# v6_io_27_28_32_33.net
KiCad netlist of a schematic drawn in Altium Designer
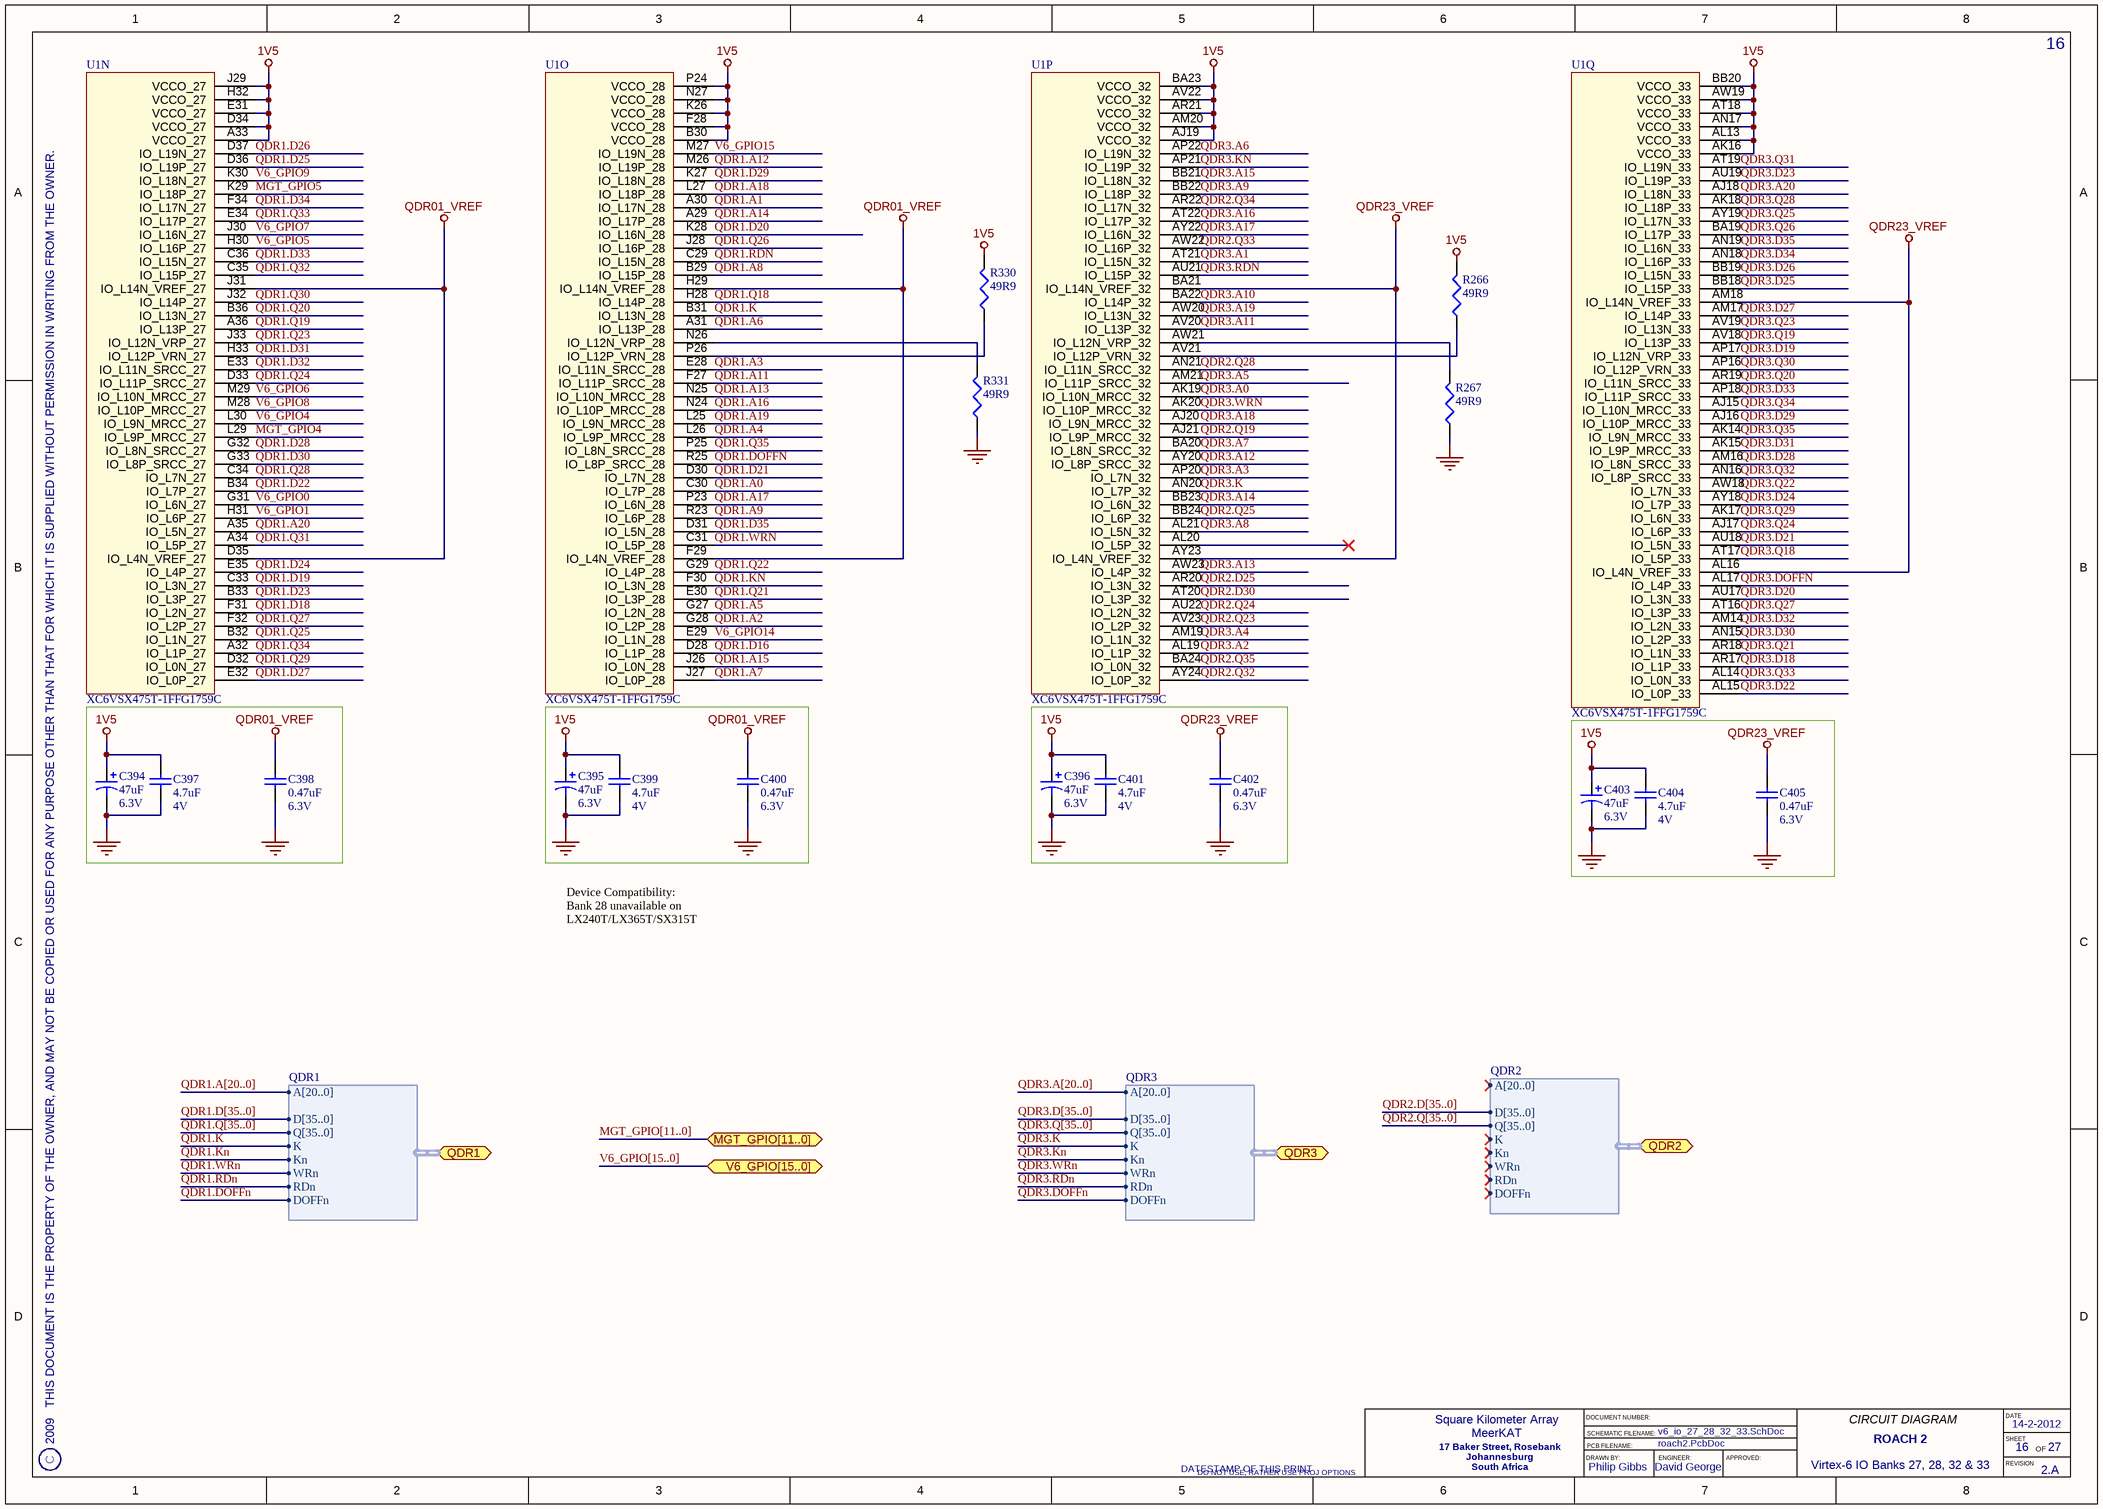
[diagram p0: v6_io_27_28_32_33.SchDoc]

(export (version "E")
  (design (tool "Eeschema 10.0.6"))
  (components
    (comp (ref "C394")
      (value "47uF")
      (footprint "CAPMP3528X120L")
      (description "47uF, Conductive Polymer Chip Capacitor")
      (fields
        (field (name "RATING") "6.3V")
        (field (name "MANUFACTURER") "KEMET")
        (field (name "PARTNUM") "T520T476M006ATE070")
      )
      (libsource (lib "altium_db") (part "CapPol"))
    )
    (comp (ref "C395")
      (value "47uF")
      (footprint "CAPMP3528X120L")
      (description "47uF, Conductive Polymer Chip Capacitor")
      (fields
        (field (name "RATING") "6.3V")
        (field (name "MANUFACTURER") "KEMET")
        (field (name "PARTNUM") "T520T476M006ATE070")
      )
      (libsource (lib "altium_db") (part "CapPol"))
    )
    (comp (ref "C396")
      (value "47uF")
      (footprint "CAPMP3528X120L")
      (description "47uF, Conductive Polymer Chip Capacitor")
      (fields
        (field (name "RATING") "6.3V")
        (field (name "MANUFACTURER") "KEMET")
        (field (name "PARTNUM") "T520T476M006ATE070")
      )
      (libsource (lib "altium_db") (part "CapPol"))
    )
    (comp (ref "C397")
      (value "4.7uF")
      (footprint "CAPC1005X60L")
      (description "4.7uF, Ceramic Capacitor")
      (fields
        (field (name "RATING") "4V")
        (field (name "MANUFACTURER") "MURATA")
        (field (name "PARTNUM") "AMK105BJ475MV-F")
      )
      (libsource (lib "altium_db") (part "CapStd"))
    )
    (comp (ref "C398")
      (value "0.47uF")
      (footprint "CAPC1005X55L")
      (description "0.47uF, Ceramic Capacitor")
      (fields
        (field (name "RATING") "6.3V")
        (field (name "MANUFACTURER") "MURATA")
        (field (name "PARTNUM") "GRM155R60J474KE19")
      )
      (libsource (lib "altium_db") (part "CapStd"))
    )
    (comp (ref "C399")
      (value "4.7uF")
      (footprint "CAPC1005X60L")
      (description "4.7uF, Ceramic Capacitor")
      (fields
        (field (name "RATING") "4V")
        (field (name "MANUFACTURER") "MURATA")
        (field (name "PARTNUM") "AMK105BJ475MV-F")
      )
      (libsource (lib "altium_db") (part "CapStd"))
    )
    (comp (ref "C400")
      (value "0.47uF")
      (footprint "CAPC1005X55L")
      (description "0.47uF, Ceramic Capacitor")
      (fields
        (field (name "RATING") "6.3V")
        (field (name "MANUFACTURER") "MURATA")
        (field (name "PARTNUM") "GRM155R60J474KE19")
      )
      (libsource (lib "altium_db") (part "CapStd"))
    )
    (comp (ref "C401")
      (value "4.7uF")
      (footprint "CAPC1005X60L")
      (description "4.7uF, Ceramic Capacitor")
      (fields
        (field (name "RATING") "4V")
        (field (name "MANUFACTURER") "MURATA")
        (field (name "PARTNUM") "AMK105BJ475MV-F")
      )
      (libsource (lib "altium_db") (part "CapStd"))
    )
    (comp (ref "C402")
      (value "0.47uF")
      (footprint "CAPC1005X55L")
      (description "0.47uF, Ceramic Capacitor")
      (fields
        (field (name "RATING") "6.3V")
        (field (name "MANUFACTURER") "MURATA")
        (field (name "PARTNUM") "GRM155R60J474KE19")
      )
      (libsource (lib "altium_db") (part "CapStd"))
    )
    (comp (ref "C403")
      (value "47uF")
      (footprint "CAPMP3528X120L")
      (description "47uF, Conductive Polymer Chip Capacitor")
      (fields
        (field (name "RATING") "6.3V")
        (field (name "MANUFACTURER") "KEMET")
        (field (name "PARTNUM") "T520T476M006ATE070")
      )
      (libsource (lib "altium_db") (part "CapPol"))
    )
    (comp (ref "C404")
      (value "4.7uF")
      (footprint "CAPC1005X60L")
      (description "4.7uF, Ceramic Capacitor")
      (fields
        (field (name "RATING") "4V")
        (field (name "MANUFACTURER") "MURATA")
        (field (name "PARTNUM") "AMK105BJ475MV-F")
      )
      (libsource (lib "altium_db") (part "CapStd"))
    )
    (comp (ref "C405")
      (value "0.47uF")
      (footprint "CAPC1005X55L")
      (description "0.47uF, Ceramic Capacitor")
      (fields
        (field (name "RATING") "6.3V")
        (field (name "MANUFACTURER") "MURATA")
        (field (name "PARTNUM") "GRM155R60J474KE19")
      )
      (libsource (lib "altium_db") (part "CapStd"))
    )
    (comp (ref "R266")
      (value "49R9")
      (footprint "RESC1005X40L")
      (description "49R9, 1.1mm x 0.5mm, Thick Film Resistor")
      (fields (field (name "MANUFACTURER") "ROYALOHM") (field (name "PARTNUM") "0402WGF499JT1E"))
      (libsource (lib "altium_db") (part "ResStd"))
    )
    (comp (ref "R267")
      (value "49R9")
      (footprint "RESC1005X40L")
      (description "49R9, 1.1mm x 0.5mm, Thick Film Resistor")
      (fields (field (name "MANUFACTURER") "ROYALOHM") (field (name "PARTNUM") "0402WGF499JT1E"))
      (libsource (lib "altium_db") (part "ResStd"))
    )
    (comp (ref "R330")
      (value "49R9")
      (footprint "RESC1005X40L")
      (description "49R9, 1.1mm x 0.5mm, Thick Film Resistor")
      (fields (field (name "MANUFACTURER") "ROYALOHM") (field (name "PARTNUM") "0402WGF499JT1E"))
      (libsource (lib "altium_db") (part "ResStd"))
    )
    (comp (ref "R331")
      (value "49R9")
      (footprint "RESC1005X40L")
      (description "49R9, 1.1mm x 0.5mm, Thick Film Resistor")
      (fields (field (name "MANUFACTURER") "ROYALOHM") (field (name "PARTNUM") "0402WGF499JT1E"))
      (libsource (lib "altium_db") (part "ResStd"))
    )
    (comp (ref "U1")
      (value "XC6VSX475T-1FFG1759C")
      (footprint "FFG1759")
      (description "Virtex-6 475SXT 1760-pin FPGA")
      (fields (field (name "MANUFACTURER") "Xilinx"))
      (libsource (lib "altium_db") (part "XC6VSX475T-1FFG1759C"))
    )
  )
  (nets
    (net (code "135") (name "/MGT_GPIO4") (class "Default")
      (node (ref "U1") (pin "L29") (pinfunction "IO_L9P_MRCC_27_L29") (pintype "passive"))
    )
    (net (code "136") (name "/MGT_GPIO5") (class "Default")
      (node (ref "U1") (pin "K29") (pinfunction "IO_L18P_27_K29") (pintype "passive"))
    )
    (net (code "138") (name "/QDR1.A0") (class "Default")
      (node (ref "U1") (pin "C30") (pinfunction "IO_L7P_28_C30") (pintype "passive"))
    )
    (net (code "139") (name "/QDR1.A1") (class "Default")
      (node (ref "U1") (pin "A30") (pinfunction "IO_L17N_28_A30") (pintype "passive"))
    )
    (net (code "140") (name "/QDR1.A2") (class "Default")
      (node (ref "U1") (pin "G28") (pinfunction "IO_L2P_28_G28") (pintype "passive"))
    )
    (net (code "141") (name "/QDR1.A3") (class "Default")
      (node (ref "U1") (pin "E28") (pinfunction "IO_L11N_SRCC_28_E28") (pintype "passive"))
    )
    (net (code "142") (name "/QDR1.A4") (class "Default")
      (node (ref "U1") (pin "L26") (pinfunction "IO_L9P_MRCC_28_L26") (pintype "passive"))
    )
    (net (code "143") (name "/QDR1.A5") (class "Default")
      (node (ref "U1") (pin "G27") (pinfunction "IO_L2N_28_G27") (pintype "passive"))
    )
    (net (code "144") (name "/QDR1.A6") (class "Default")
      (node (ref "U1") (pin "A31") (pinfunction "IO_L13P_28_A31") (pintype "passive"))
    )
    (net (code "145") (name "/QDR1.A7") (class "Default")
      (node (ref "U1") (pin "J27") (pinfunction "IO_L0P_28_J27") (pintype "passive"))
    )
    (net (code "146") (name "/QDR1.A8") (class "Default")
      (node (ref "U1") (pin "B29") (pinfunction "IO_L15P_28_B29") (pintype "passive"))
    )
    (net (code "147") (name "/QDR1.A9") (class "Default")
      (node (ref "U1") (pin "R23") (pinfunction "IO_L6P_28_R23") (pintype "passive"))
    )
    (net (code "148") (name "/QDR1.A11") (class "Default")
      (node (ref "U1") (pin "F27") (pinfunction "IO_L11P_SRCC_28_F27") (pintype "passive"))
    )
    (net (code "149") (name "/QDR1.A12") (class "Default")
      (node (ref "U1") (pin "M26") (pinfunction "IO_L19P_28_M26") (pintype "passive"))
    )
    (net (code "150") (name "/QDR1.A13") (class "Default")
      (node (ref "U1") (pin "N25") (pinfunction "IO_L10N_MRCC_28_N25") (pintype "passive"))
    )
    (net (code "151") (name "/QDR1.A14") (class "Default")
      (node (ref "U1") (pin "A29") (pinfunction "IO_L17P_28_A29") (pintype "passive"))
    )
    (net (code "152") (name "/QDR1.A15") (class "Default")
      (node (ref "U1") (pin "J26") (pinfunction "IO_L0N_28_J26") (pintype "passive"))
    )
    (net (code "153") (name "/QDR1.A16") (class "Default")
      (node (ref "U1") (pin "N24") (pinfunction "IO_L10P_MRCC_28_N24") (pintype "passive"))
    )
    (net (code "154") (name "/QDR1.A17") (class "Default")
      (node (ref "U1") (pin "P23") (pinfunction "IO_L6N_28_P23") (pintype "passive"))
    )
    (net (code "155") (name "/QDR1.A18") (class "Default")
      (node (ref "U1") (pin "L27") (pinfunction "IO_L18P_28_L27") (pintype "passive"))
    )
    (net (code "156") (name "/QDR1.A19") (class "Default")
      (node (ref "U1") (pin "L25") (pinfunction "IO_L9N_MRCC_28_L25") (pintype "passive"))
    )
    (net (code "157") (name "/QDR1.A20") (class "Default")
      (node (ref "U1") (pin "A35") (pinfunction "IO_L5N_27_A35") (pintype "passive"))
    )
    (net (code "159") (name "/QDR1.D16") (class "Default")
      (node (ref "U1") (pin "D28") (pinfunction "IO_L1P_28_D28") (pintype "passive"))
    )
    (net (code "160") (name "/QDR1.D18") (class "Default")
      (node (ref "U1") (pin "F31") (pinfunction "IO_L2N_27_F31") (pintype "passive"))
    )
    (net (code "161") (name "/QDR1.D19") (class "Default")
      (node (ref "U1") (pin "C33") (pinfunction "IO_L3N_27_C33") (pintype "passive"))
    )
    (net (code "162") (name "/QDR1.D20") (class "Default")
      (node (ref "U1") (pin "K28") (pinfunction "IO_L16N_28_K28") (pintype "passive"))
    )
    (net (code "163") (name "/QDR1.D21") (class "Default")
      (node (ref "U1") (pin "D30") (pinfunction "IO_L7N_28_D30") (pintype "passive"))
    )
    (net (code "164") (name "/QDR1.D22") (class "Default")
      (node (ref "U1") (pin "B34") (pinfunction "IO_L7P_27_B34") (pintype "passive"))
    )
    (net (code "165") (name "/QDR1.D23") (class "Default")
      (node (ref "U1") (pin "B33") (pinfunction "IO_L3P_27_B33") (pintype "passive"))
    )
    (net (code "166") (name "/QDR1.D24") (class "Default")
      (node (ref "U1") (pin "E35") (pinfunction "IO_L4P_27_E35") (pintype "passive"))
    )
    (net (code "167") (name "/QDR1.D25") (class "Default")
      (node (ref "U1") (pin "D36") (pinfunction "IO_L19P_27_D36") (pintype "passive"))
    )
    (net (code "168") (name "/QDR1.D26") (class "Default")
      (node (ref "U1") (pin "D37") (pinfunction "IO_L19N_27_D37") (pintype "passive"))
    )
    (net (code "169") (name "/QDR1.D27") (class "Default")
      (node (ref "U1") (pin "E32") (pinfunction "IO_L0P_27_E32") (pintype "passive"))
    )
    (net (code "170") (name "/QDR1.D28") (class "Default")
      (node (ref "U1") (pin "G32") (pinfunction "IO_L8N_SRCC_27_G32") (pintype "passive"))
    )
    (net (code "171") (name "/QDR1.D29") (class "Default")
      (node (ref "U1") (pin "K27") (pinfunction "IO_L18N_28_K27") (pintype "passive"))
    )
    (net (code "172") (name "/QDR1.D30") (class "Default")
      (node (ref "U1") (pin "G33") (pinfunction "IO_L8P_SRCC_27_G33") (pintype "passive"))
    )
    (net (code "173") (name "/QDR1.D31") (class "Default")
      (node (ref "U1") (pin "H33") (pinfunction "IO_L12P_VRN_27_H33") (pintype "passive"))
    )
    (net (code "174") (name "/QDR1.D32") (class "Default")
      (node (ref "U1") (pin "E33") (pinfunction "IO_L11N_SRCC_27_E33") (pintype "passive"))
    )
    (net (code "175") (name "/QDR1.D33") (class "Default")
      (node (ref "U1") (pin "C36") (pinfunction "IO_L15N_27_C36") (pintype "passive"))
    )
    (net (code "176") (name "/QDR1.D34") (class "Default")
      (node (ref "U1") (pin "F34") (pinfunction "IO_L17N_27_F34") (pintype "passive"))
    )
    (net (code "177") (name "/QDR1.D35") (class "Default")
      (node (ref "U1") (pin "D31") (pinfunction "IO_L5N_28_D31") (pintype "passive"))
    )
    (net (code "178") (name "/QDR1.DOFFN") (class "Default")
      (node (ref "U1") (pin "R25") (pinfunction "IO_L8P_SRCC_28_R25") (pintype "passive"))
    )
    (net (code "181") (name "/QDR1.K") (class "Default")
      (node (ref "U1") (pin "B31") (pinfunction "IO_L13N_28_B31") (pintype "passive"))
    )
    (net (code "182") (name "/QDR1.KN") (class "Default")
      (node (ref "U1") (pin "F30") (pinfunction "IO_L3N_28_F30") (pintype "passive"))
    )
    (net (code "184") (name "/QDR1.Q18") (class "Default")
      (node (ref "U1") (pin "H28") (pinfunction "IO_L14P_28_H28") (pintype "passive"))
    )
    (net (code "185") (name "/QDR1.Q19") (class "Default")
      (node (ref "U1") (pin "A36") (pinfunction "IO_L13P_27_A36") (pintype "passive"))
    )
    (net (code "186") (name "/QDR1.Q20") (class "Default")
      (node (ref "U1") (pin "B36") (pinfunction "IO_L13N_27_B36") (pintype "passive"))
    )
    (net (code "187") (name "/QDR1.Q21") (class "Default")
      (node (ref "U1") (pin "E30") (pinfunction "IO_L3P_28_E30") (pintype "passive"))
    )
    (net (code "188") (name "/QDR1.Q22") (class "Default")
      (node (ref "U1") (pin "G29") (pinfunction "IO_L4P_28_G29") (pintype "passive"))
    )
    (net (code "189") (name "/QDR1.Q23") (class "Default")
      (node (ref "U1") (pin "J33") (pinfunction "IO_L12N_VRP_27_J33") (pintype "passive"))
    )
    (net (code "190") (name "/QDR1.Q24") (class "Default")
      (node (ref "U1") (pin "D33") (pinfunction "IO_L11P_SRCC_27_D33") (pintype "passive"))
    )
    (net (code "191") (name "/QDR1.Q25") (class "Default")
      (node (ref "U1") (pin "B32") (pinfunction "IO_L1N_27_B32") (pintype "passive"))
    )
    (net (code "192") (name "/QDR1.Q26") (class "Default")
      (node (ref "U1") (pin "J28") (pinfunction "IO_L16P_28_J28") (pintype "passive"))
    )
    (net (code "193") (name "/QDR1.Q27") (class "Default")
      (node (ref "U1") (pin "F32") (pinfunction "IO_L2P_27_F32") (pintype "passive"))
    )
    (net (code "194") (name "/QDR1.Q28") (class "Default")
      (node (ref "U1") (pin "C34") (pinfunction "IO_L7N_27_C34") (pintype "passive"))
    )
    (net (code "195") (name "/QDR1.Q29") (class "Default")
      (node (ref "U1") (pin "D32") (pinfunction "IO_L0N_27_D32") (pintype "passive"))
    )
    (net (code "196") (name "/QDR1.Q30") (class "Default")
      (node (ref "U1") (pin "J32") (pinfunction "IO_L14P_27_J32") (pintype "passive"))
    )
    (net (code "197") (name "/QDR1.Q31") (class "Default")
      (node (ref "U1") (pin "A34") (pinfunction "IO_L5P_27_A34") (pintype "passive"))
    )
    (net (code "198") (name "/QDR1.Q32") (class "Default")
      (node (ref "U1") (pin "C35") (pinfunction "IO_L15P_27_C35") (pintype "passive"))
    )
    (net (code "199") (name "/QDR1.Q33") (class "Default")
      (node (ref "U1") (pin "E34") (pinfunction "IO_L17P_27_E34") (pintype "passive"))
    )
    (net (code "200") (name "/QDR1.Q34") (class "Default")
      (node (ref "U1") (pin "A32") (pinfunction "IO_L1P_27_A32") (pintype "passive"))
    )
    (net (code "201") (name "/QDR1.Q35") (class "Default")
      (node (ref "U1") (pin "P25") (pinfunction "IO_L8N_SRCC_28_P25") (pintype "passive"))
    )
    (net (code "202") (name "/QDR1.RDN") (class "Default")
      (node (ref "U1") (pin "C29") (pinfunction "IO_L15N_28_C29") (pintype "passive"))
    )
    (net (code "204") (name "/QDR1.WRN") (class "Default")
      (node (ref "U1") (pin "C31") (pinfunction "IO_L5P_28_C31") (pintype "passive"))
    )
    (net (code "207") (name "/QDR2.D25") (class "Default")
      (node (ref "U1") (pin "AR20") (pinfunction "IO_L3N_32_AR20") (pintype "passive"))
    )
    (net (code "208") (name "/QDR2.D30") (class "Default")
      (node (ref "U1") (pin "AT20") (pinfunction "IO_L3P_32_AT20") (pintype "passive"))
    )
    (net (code "210") (name "/QDR2.Q19") (class "Default")
      (node (ref "U1") (pin "AJ21") (pinfunction "IO_L9P_MRCC_32_AJ21") (pintype "passive"))
    )
    (net (code "211") (name "/QDR2.Q23") (class "Default")
      (node (ref "U1") (pin "AV23") (pinfunction "IO_L2P_32_AV23") (pintype "passive"))
    )
    (net (code "212") (name "/QDR2.Q24") (class "Default")
      (node (ref "U1") (pin "AU22") (pinfunction "IO_L2N_32_AU22") (pintype "passive"))
    )
    (net (code "213") (name "/QDR2.Q25") (class "Default")
      (node (ref "U1") (pin "BB24") (pinfunction "IO_L6P_32_BB24") (pintype "passive"))
    )
    (net (code "214") (name "/QDR2.Q28") (class "Default")
      (node (ref "U1") (pin "AN21") (pinfunction "IO_L11N_SRCC_32_AN21") (pintype "passive"))
    )
    (net (code "215") (name "/QDR2.Q32") (class "Default")
      (node (ref "U1") (pin "AY24") (pinfunction "IO_L0P_32_AY24") (pintype "passive"))
    )
    (net (code "216") (name "/QDR2.Q33") (class "Default")
      (node (ref "U1") (pin "AW22") (pinfunction "IO_L16P_32_AW22") (pintype "passive"))
    )
    (net (code "217") (name "/QDR2.Q34") (class "Default")
      (node (ref "U1") (pin "AR22") (pinfunction "IO_L17N_32_AR22") (pintype "passive"))
    )
    (net (code "218") (name "/QDR2.Q35") (class "Default")
      (node (ref "U1") (pin "BA24") (pinfunction "IO_L0N_32_BA24") (pintype "passive"))
    )
    (net (code "220") (name "/QDR3.A0") (class "Default")
      (node (ref "U1") (pin "AK19") (pinfunction "IO_L10N_MRCC_32_AK19") (pintype "passive"))
    )
    (net (code "221") (name "/QDR3.A1") (class "Default")
      (node (ref "U1") (pin "AT21") (pinfunction "IO_L15N_32_AT21") (pintype "passive"))
    )
    (net (code "222") (name "/QDR3.A2") (class "Default")
      (node (ref "U1") (pin "AL19") (pinfunction "IO_L1P_32_AL19") (pintype "passive"))
    )
    (net (code "223") (name "/QDR3.A3") (class "Default")
      (node (ref "U1") (pin "AP20") (pinfunction "IO_L7N_32_AP20") (pintype "passive"))
    )
    (net (code "224") (name "/QDR3.A4") (class "Default")
      (node (ref "U1") (pin "AM19") (pinfunction "IO_L1N_32_AM19") (pintype "passive"))
    )
    (net (code "225") (name "/QDR3.A5") (class "Default")
      (node (ref "U1") (pin "AM21") (pinfunction "IO_L11P_SRCC_32_AM21") (pintype "passive"))
    )
    (net (code "226") (name "/QDR3.A6") (class "Default")
      (node (ref "U1") (pin "AP22") (pinfunction "IO_L19N_32_AP22") (pintype "passive"))
    )
    (net (code "227") (name "/QDR3.A7") (class "Default")
      (node (ref "U1") (pin "BA20") (pinfunction "IO_L8N_SRCC_32_BA20") (pintype "passive"))
    )
    (net (code "228") (name "/QDR3.A8") (class "Default")
      (node (ref "U1") (pin "AL21") (pinfunction "IO_L5N_32_AL21") (pintype "passive"))
    )
    (net (code "229") (name "/QDR3.A9") (class "Default")
      (node (ref "U1") (pin "BB22") (pinfunction "IO_L18P_32_BB22") (pintype "passive"))
    )
    (net (code "230") (name "/QDR3.A10") (class "Default")
      (node (ref "U1") (pin "BA22") (pinfunction "IO_L14P_32_BA22") (pintype "passive"))
    )
    (net (code "231") (name "/QDR3.A11") (class "Default")
      (node (ref "U1") (pin "AV20") (pinfunction "IO_L13P_32_AV20") (pintype "passive"))
    )
    (net (code "232") (name "/QDR3.A12") (class "Default")
      (node (ref "U1") (pin "AY20") (pinfunction "IO_L8P_SRCC_32_AY20") (pintype "passive"))
    )
    (net (code "233") (name "/QDR3.A13") (class "Default")
      (node (ref "U1") (pin "AW23") (pinfunction "IO_L4P_32_AW23") (pintype "passive"))
    )
    (net (code "234") (name "/QDR3.A14") (class "Default")
      (node (ref "U1") (pin "BB23") (pinfunction "IO_L6N_32_BB23") (pintype "passive"))
    )
    (net (code "235") (name "/QDR3.A15") (class "Default")
      (node (ref "U1") (pin "BB21") (pinfunction "IO_L18N_32_BB21") (pintype "passive"))
    )
    (net (code "236") (name "/QDR3.A16") (class "Default")
      (node (ref "U1") (pin "AT22") (pinfunction "IO_L17P_32_AT22") (pintype "passive"))
    )
    (net (code "237") (name "/QDR3.A17") (class "Default")
      (node (ref "U1") (pin "AY22") (pinfunction "IO_L16N_32_AY22") (pintype "passive"))
    )
    (net (code "238") (name "/QDR3.A18") (class "Default")
      (node (ref "U1") (pin "AJ20") (pinfunction "IO_L9N_MRCC_32_AJ20") (pintype "passive"))
    )
    (net (code "239") (name "/QDR3.A19") (class "Default")
      (node (ref "U1") (pin "AW20") (pinfunction "IO_L13N_32_AW20") (pintype "passive"))
    )
    (net (code "240") (name "/QDR3.A20") (class "Default")
      (node (ref "U1") (pin "AJ18") (pinfunction "IO_L18N_33_AJ18") (pintype "passive"))
    )
    (net (code "242") (name "/QDR3.D18") (class "Default")
      (node (ref "U1") (pin "AR17") (pinfunction "IO_L1P_33_AR17") (pintype "passive"))
    )
    (net (code "243") (name "/QDR3.D19") (class "Default")
      (node (ref "U1") (pin "AP17") (pinfunction "IO_L12N_VRP_33_AP17") (pintype "passive"))
    )
    (net (code "244") (name "/QDR3.D20") (class "Default")
      (node (ref "U1") (pin "AU17") (pinfunction "IO_L3N_33_AU17") (pintype "passive"))
    )
    (net (code "245") (name "/QDR3.D21") (class "Default")
      (node (ref "U1") (pin "AU18") (pinfunction "IO_L5N_33_AU18") (pintype "passive"))
    )
    (net (code "246") (name "/QDR3.D22") (class "Default")
      (node (ref "U1") (pin "AL15") (pinfunction "IO_L0P_33_AL15") (pintype "passive"))
    )
    (net (code "247") (name "/QDR3.D23") (class "Default")
      (node (ref "U1") (pin "AU19") (pinfunction "IO_L19P_33_AU19") (pintype "passive"))
    )
    (net (code "248") (name "/QDR3.D24") (class "Default")
      (node (ref "U1") (pin "AY18") (pinfunction "IO_L7P_33_AY18") (pintype "passive"))
    )
    (net (code "249") (name "/QDR3.D25") (class "Default")
      (node (ref "U1") (pin "BB18") (pinfunction "IO_L15P_33_BB18") (pintype "passive"))
    )
    (net (code "250") (name "/QDR3.D26") (class "Default")
      (node (ref "U1") (pin "BB19") (pinfunction "IO_L15N_33_BB19") (pintype "passive"))
    )
    (net (code "251") (name "/QDR3.D27") (class "Default")
      (node (ref "U1") (pin "AM17") (pinfunction "IO_L14P_33_AM17") (pintype "passive"))
    )
    (net (code "252") (name "/QDR3.D28") (class "Default")
      (node (ref "U1") (pin "AM16") (pinfunction "IO_L8N_SRCC_33_AM16") (pintype "passive"))
    )
    (net (code "253") (name "/QDR3.D29") (class "Default")
      (node (ref "U1") (pin "AJ16") (pinfunction "IO_L10P_MRCC_33_AJ16") (pintype "passive"))
    )
    (net (code "254") (name "/QDR3.D30") (class "Default")
      (node (ref "U1") (pin "AN15") (pinfunction "IO_L2P_33_AN15") (pintype "passive"))
    )
    (net (code "255") (name "/QDR3.D31") (class "Default")
      (node (ref "U1") (pin "AK15") (pinfunction "IO_L9P_MRCC_33_AK15") (pintype "passive"))
    )
    (net (code "256") (name "/QDR3.D32") (class "Default")
      (node (ref "U1") (pin "AM14") (pinfunction "IO_L2N_33_AM14") (pintype "passive"))
    )
    (net (code "257") (name "/QDR3.D33") (class "Default")
      (node (ref "U1") (pin "AP18") (pinfunction "IO_L11P_SRCC_33_AP18") (pintype "passive"))
    )
    (net (code "258") (name "/QDR3.D34") (class "Default")
      (node (ref "U1") (pin "AN18") (pinfunction "IO_L16P_33_AN18") (pintype "passive"))
    )
    (net (code "259") (name "/QDR3.D35") (class "Default")
      (node (ref "U1") (pin "AN19") (pinfunction "IO_L16N_33_AN19") (pintype "passive"))
    )
    (net (code "260") (name "/QDR3.DOFFN") (class "Default")
      (node (ref "U1") (pin "AL17") (pinfunction "IO_L4P_33_AL17") (pintype "passive"))
    )
    (net (code "263") (name "/QDR3.K") (class "Default")
      (node (ref "U1") (pin "AN20") (pinfunction "IO_L7P_32_AN20") (pintype "passive"))
    )
    (net (code "264") (name "/QDR3.KN") (class "Default")
      (node (ref "U1") (pin "AP21") (pinfunction "IO_L19P_32_AP21") (pintype "passive"))
    )
    (net (code "266") (name "/QDR3.Q18") (class "Default")
      (node (ref "U1") (pin "AT17") (pinfunction "IO_L5P_33_AT17") (pintype "passive"))
    )
    (net (code "267") (name "/QDR3.Q19") (class "Default")
      (node (ref "U1") (pin "AV18") (pinfunction "IO_L13P_33_AV18") (pintype "passive"))
    )
    (net (code "268") (name "/QDR3.Q20") (class "Default")
      (node (ref "U1") (pin "AR19") (pinfunction "IO_L11N_SRCC_33_AR19") (pintype "passive"))
    )
    (net (code "269") (name "/QDR3.Q21") (class "Default")
      (node (ref "U1") (pin "AR18") (pinfunction "IO_L1N_33_AR18") (pintype "passive"))
    )
    (net (code "270") (name "/QDR3.Q22") (class "Default")
      (node (ref "U1") (pin "AW18") (pinfunction "IO_L7N_33_AW18") (pintype "passive"))
    )
    (net (code "271") (name "/QDR3.Q23") (class "Default")
      (node (ref "U1") (pin "AV19") (pinfunction "IO_L13N_33_AV19") (pintype "passive"))
    )
    (net (code "272") (name "/QDR3.Q24") (class "Default")
      (node (ref "U1") (pin "AJ17") (pinfunction "IO_L6P_33_AJ17") (pintype "passive"))
    )
    (net (code "273") (name "/QDR3.Q25") (class "Default")
      (node (ref "U1") (pin "AY19") (pinfunction "IO_L17N_33_AY19") (pintype "passive"))
    )
    (net (code "274") (name "/QDR3.Q26") (class "Default")
      (node (ref "U1") (pin "BA19") (pinfunction "IO_L17P_33_BA19") (pintype "passive"))
    )
    (net (code "275") (name "/QDR3.Q27") (class "Default")
      (node (ref "U1") (pin "AT16") (pinfunction "IO_L3P_33_AT16") (pintype "passive"))
    )
    (net (code "276") (name "/QDR3.Q28") (class "Default")
      (node (ref "U1") (pin "AK18") (pinfunction "IO_L18P_33_AK18") (pintype "passive"))
    )
    (net (code "277") (name "/QDR3.Q29") (class "Default")
      (node (ref "U1") (pin "AK17") (pinfunction "IO_L6N_33_AK17") (pintype "passive"))
    )
    (net (code "278") (name "/QDR3.Q30") (class "Default")
      (node (ref "U1") (pin "AP16") (pinfunction "IO_L12P_VRN_33_AP16") (pintype "passive"))
    )
    (net (code "279") (name "/QDR3.Q31") (class "Default")
      (node (ref "U1") (pin "AT19") (pinfunction "IO_L19N_33_AT19") (pintype "passive"))
    )
    (net (code "280") (name "/QDR3.Q32") (class "Default")
      (node (ref "U1") (pin "AN16") (pinfunction "IO_L8P_SRCC_33_AN16") (pintype "passive"))
    )
    (net (code "281") (name "/QDR3.Q33") (class "Default")
      (node (ref "U1") (pin "AL14") (pinfunction "IO_L0N_33_AL14") (pintype "passive"))
    )
    (net (code "282") (name "/QDR3.Q34") (class "Default")
      (node (ref "U1") (pin "AJ15") (pinfunction "IO_L10N_MRCC_33_AJ15") (pintype "passive"))
    )
    (net (code "283") (name "/QDR3.Q35") (class "Default")
      (node (ref "U1") (pin "AK14") (pinfunction "IO_L9N_MRCC_33_AK14") (pintype "passive"))
    )
    (net (code "285") (name "/QDR3.RDN") (class "Default")
      (node (ref "U1") (pin "AU21") (pinfunction "IO_L15P_32_AU21") (pintype "passive"))
    )
    (net (code "287") (name "/QDR3.WRN") (class "Default")
      (node (ref "U1") (pin "AK20") (pinfunction "IO_L10P_MRCC_32_AK20") (pintype "passive"))
    )
    (net (code "289") (name "/V6_GPIO0") (class "Default")
      (node (ref "U1") (pin "G31") (pinfunction "IO_L6N_27_G31") (pintype "passive"))
    )
    (net (code "290") (name "/V6_GPIO1") (class "Default")
      (node (ref "U1") (pin "H31") (pinfunction "IO_L6P_27_H31") (pintype "passive"))
    )
    (net (code "291") (name "/V6_GPIO4") (class "Default")
      (node (ref "U1") (pin "L30") (pinfunction "IO_L9N_MRCC_27_L30") (pintype "passive"))
    )
    (net (code "292") (name "/V6_GPIO5") (class "Default")
      (node (ref "U1") (pin "H30") (pinfunction "IO_L16P_27_H30") (pintype "passive"))
    )
    (net (code "293") (name "/V6_GPIO6") (class "Default")
      (node (ref "U1") (pin "M29") (pinfunction "IO_L10N_MRCC_27_M29") (pintype "passive"))
    )
    (net (code "294") (name "/V6_GPIO7") (class "Default")
      (node (ref "U1") (pin "J30") (pinfunction "IO_L16N_27_J30") (pintype "passive"))
    )
    (net (code "295") (name "/V6_GPIO8") (class "Default")
      (node (ref "U1") (pin "M28") (pinfunction "IO_L10P_MRCC_27_M28") (pintype "passive"))
    )
    (net (code "296") (name "/V6_GPIO9") (class "Default")
      (node (ref "U1") (pin "K30") (pinfunction "IO_L18N_27_K30") (pintype "passive"))
    )
    (net (code "297") (name "/V6_GPIO14") (class "Default")
      (node (ref "U1") (pin "E29") (pinfunction "IO_L1N_28_E29") (pintype "passive"))
    )
    (net (code "298") (name "/V6_GPIO15") (class "Default")
      (node (ref "U1") (pin "M27") (pinfunction "IO_L19N_28_M27") (pintype "passive"))
    )
    (net (code "303") (name "1V5") (class "Default")
      (node (ref "C394") (pin "1") (pinfunction "1_1") (pintype "passive"))
      (node (ref "C395") (pin "1") (pinfunction "1_1") (pintype "passive"))
      (node (ref "C396") (pin "1") (pinfunction "1_1") (pintype "passive"))
      (node (ref "C397") (pin "2") (pinfunction "2_2") (pintype "passive"))
      (node (ref "C399") (pin "2") (pinfunction "2_2") (pintype "passive"))
      (node (ref "C401") (pin "2") (pinfunction "2_2") (pintype "passive"))
      (node (ref "C403") (pin "1") (pinfunction "1_1") (pintype "passive"))
      (node (ref "C404") (pin "2") (pinfunction "2_2") (pintype "passive"))
      (node (ref "R266") (pin "2") (pinfunction "2_2") (pintype "passive"))
      (node (ref "R330") (pin "2") (pinfunction "2_2") (pintype "passive"))
      (node (ref "U1") (pin "A33") (pinfunction "VCCO_27_A33") (pintype "passive"))
      (node (ref "U1") (pin "AJ19") (pinfunction "VCCO_32_AJ19") (pintype "passive"))
      (node (ref "U1") (pin "AK16") (pinfunction "VCCO_33_AK16") (pintype "passive"))
      (node (ref "U1") (pin "AL13") (pinfunction "VCCO_33_AL13") (pintype "passive"))
      (node (ref "U1") (pin "AM20") (pinfunction "VCCO_32_AM20") (pintype "passive"))
      (node (ref "U1") (pin "AN17") (pinfunction "VCCO_33_AN17") (pintype "passive"))
      (node (ref "U1") (pin "AR21") (pinfunction "VCCO_32_AR21") (pintype "passive"))
      (node (ref "U1") (pin "AT18") (pinfunction "VCCO_33_AT18") (pintype "passive"))
      (node (ref "U1") (pin "AV22") (pinfunction "VCCO_32_AV22") (pintype "passive"))
      (node (ref "U1") (pin "AW19") (pinfunction "VCCO_33_AW19") (pintype "passive"))
      (node (ref "U1") (pin "B30") (pinfunction "VCCO_28_B30") (pintype "passive"))
      (node (ref "U1") (pin "BA23") (pinfunction "VCCO_32_BA23") (pintype "passive"))
      (node (ref "U1") (pin "BB20") (pinfunction "VCCO_33_BB20") (pintype "passive"))
      (node (ref "U1") (pin "D34") (pinfunction "VCCO_27_D34") (pintype "passive"))
      (node (ref "U1") (pin "E31") (pinfunction "VCCO_27_E31") (pintype "passive"))
      (node (ref "U1") (pin "F28") (pinfunction "VCCO_28_F28") (pintype "passive"))
      (node (ref "U1") (pin "H32") (pinfunction "VCCO_27_H32") (pintype "passive"))
      (node (ref "U1") (pin "J29") (pinfunction "VCCO_27_J29") (pintype "passive"))
      (node (ref "U1") (pin "K26") (pinfunction "VCCO_28_K26") (pintype "passive"))
      (node (ref "U1") (pin "N27") (pinfunction "VCCO_28_N27") (pintype "passive"))
      (node (ref "U1") (pin "P24") (pinfunction "VCCO_28_P24") (pintype "passive"))
    )
    (net (code "304") (name "GND") (class "Default")
      (node (ref "C394") (pin "2") (pinfunction "2_2") (pintype "passive"))
      (node (ref "C395") (pin "2") (pinfunction "2_2") (pintype "passive"))
      (node (ref "C396") (pin "2") (pinfunction "2_2") (pintype "passive"))
      (node (ref "C397") (pin "1") (pinfunction "1_1") (pintype "passive"))
      (node (ref "C398") (pin "1") (pinfunction "1_1") (pintype "passive"))
      (node (ref "C399") (pin "1") (pinfunction "1_1") (pintype "passive"))
      (node (ref "C400") (pin "1") (pinfunction "1_1") (pintype "passive"))
      (node (ref "C401") (pin "1") (pinfunction "1_1") (pintype "passive"))
      (node (ref "C402") (pin "1") (pinfunction "1_1") (pintype "passive"))
      (node (ref "C403") (pin "2") (pinfunction "2_2") (pintype "passive"))
      (node (ref "C404") (pin "1") (pinfunction "1_1") (pintype "passive"))
      (node (ref "C405") (pin "1") (pinfunction "1_1") (pintype "passive"))
      (node (ref "R267") (pin "1") (pinfunction "1_1") (pintype "passive"))
      (node (ref "R331") (pin "1") (pinfunction "1_1") (pintype "passive"))
    )
    (net (code "305") (name "Net-(U1O-IO_L12N_VRP_28)") (class "Default")
      (node (ref "R331") (pin "2") (pinfunction "2_2") (pintype "passive"))
      (node (ref "U1") (pin "N26") (pinfunction "IO_L12N_VRP_28_N26") (pintype "passive"))
    )
    (net (code "306") (name "Net-(U1O-IO_L12P_VRN_28)") (class "Default")
      (node (ref "R330") (pin "1") (pinfunction "1_1") (pintype "passive"))
      (node (ref "U1") (pin "P26") (pinfunction "IO_L12P_VRN_28_P26") (pintype "passive"))
    )
    (net (code "307") (name "Net-(U1P-IO_L12N_VRP_32)") (class "Default")
      (node (ref "R267") (pin "2") (pinfunction "2_2") (pintype "passive"))
      (node (ref "U1") (pin "AW21") (pinfunction "IO_L12N_VRP_32_AW21") (pintype "passive"))
    )
    (net (code "308") (name "Net-(U1P-IO_L12P_VRN_32)") (class "Default")
      (node (ref "R266") (pin "1") (pinfunction "1_1") (pintype "passive"))
      (node (ref "U1") (pin "AV21") (pinfunction "IO_L12P_VRN_32_AV21") (pintype "passive"))
    )
    (net (code "309") (name "QDR01_VREF") (class "Default")
      (node (ref "C398") (pin "2") (pinfunction "2_2") (pintype "passive"))
      (node (ref "C400") (pin "2") (pinfunction "2_2") (pintype "passive"))
      (node (ref "U1") (pin "D35") (pinfunction "IO_L4N_VREF_27_D35") (pintype "passive"))
      (node (ref "U1") (pin "F29") (pinfunction "IO_L4N_VREF_28_F29") (pintype "passive"))
      (node (ref "U1") (pin "H29") (pinfunction "IO_L14N_VREF_28_H29") (pintype "passive"))
      (node (ref "U1") (pin "J31") (pinfunction "IO_L14N_VREF_27_J31") (pintype "passive"))
    )
    (net (code "310") (name "QDR23_VREF") (class "Default")
      (node (ref "C402") (pin "2") (pinfunction "2_2") (pintype "passive"))
      (node (ref "C405") (pin "2") (pinfunction "2_2") (pintype "passive"))
      (node (ref "U1") (pin "AL16") (pinfunction "IO_L4N_VREF_33_AL16") (pintype "passive"))
      (node (ref "U1") (pin "AM18") (pinfunction "IO_L14N_VREF_33_AM18") (pintype "passive"))
      (node (ref "U1") (pin "AY23") (pinfunction "IO_L4N_VREF_32_AY23") (pintype "passive"))
      (node (ref "U1") (pin "BA21") (pinfunction "IO_L14N_VREF_32_BA21") (pintype "passive"))
    )
    (net (code "311") (name "unconnected-(U1P-IO_L5P_32-PadAL20)") (class "Default")
      (node (ref "U1") (pin "AL20") (pinfunction "IO_L5P_32_AL20") (pintype "passive+no_connect"))
    )
  )
)
